# air_quality_monitor_add_esp32_chip.net
KiCad netlist of a schematic drawn in Altium Designer
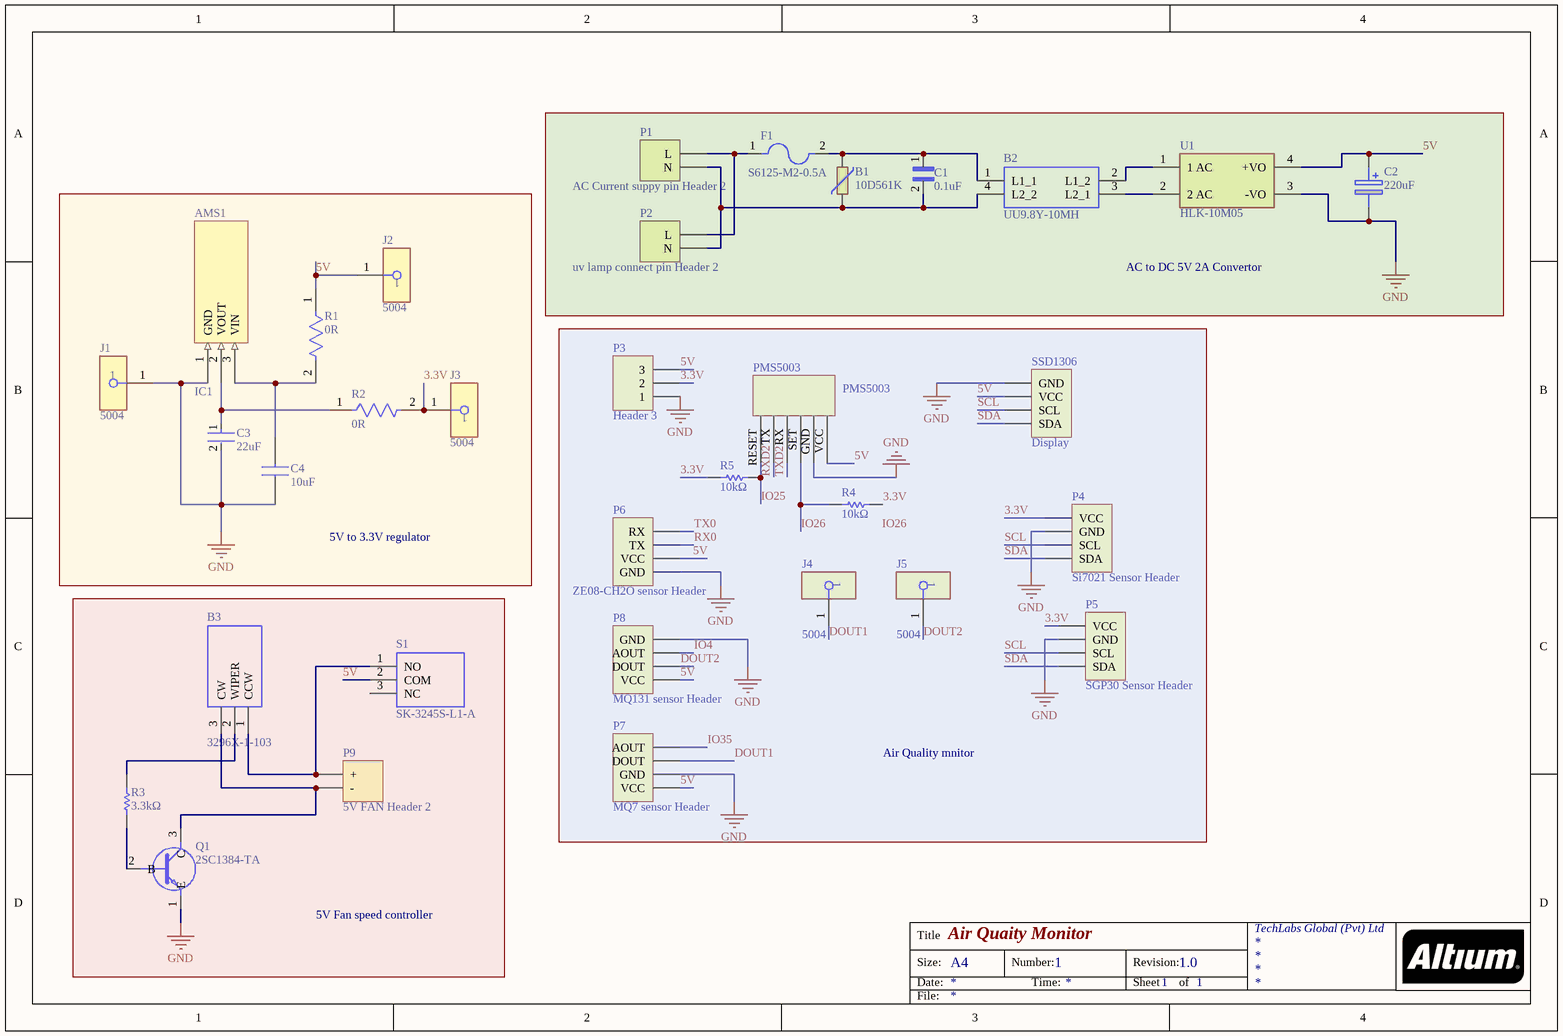
[diagram p0: air quality monitor add esp32 chip.SchDoc]

(export (version "E")
  (design (tool "Eeschema 10.0.6"))
  (components
    (comp (ref "AMS1")
      (value "IC1")
      (footprint "SOT89-150P350X150-3N")
      (fields
        (field (name "MANUFACTURER") "YONGYUTAI")
        (field (name "MFR. PART #") "AMS1117-3.3")
        (field (name "LCSC PART #") "C2904742")
      )
      (libsource (lib "AMS1117-3.3") (part "IC?"))
    )
    (comp (ref "B1")
      (value "10D561K")
      (footprint "10D561K")
      (description "920V 42.3J 180pF@1kHz 460V 350V 504V~616V 2.5kA Plugin Varistors ROHS")
      (fields (field (name "LCSC PART #") "C113236") (field (name "MANUFACTURER") "Hongzhi Elec"))
      (libsource (lib "10D561K") (part "10D561K"))
    )
    (comp (ref "B2")
      (value "UU9.8Y-10MH")
      (footprint "UU98Y10MH")
      (description "10mH@1kHz 1.2Ω 2 500mA 50V Plugin Common Mode Filters ROHS")
      (fields
        (field (name "MANUFACTURER") "FH (Guangdong Fenghua Advanced Tech)")
        (field (name "LCSC PART#") "C75192")
      )
      (libsource (lib "UU9.8Y-10MH") (part "UU9.8Y-10MH"))
    )
    (comp (ref "B3")
      (value "3296X-1-103")
      (footprint "3296X1223LF")
      (description "±10% 10kΩ Plugin Variable Resistors/Potentiometers ROHS")
      (fields
        (field (name "MANUFACTURER") "BOCHEN(Chengdu Guosheng Tech)")
        (field (name "LCSC PART #") "C118955")
      )
      (libsource (lib "3296X-1-103") (part "3296X-1-103"))
    )
    (comp (ref "C1")
      (value "0.1uF")
      (footprint "MPX-104K275VAC-C-D2")
      (description "0.1uF ±10% -40℃~+110℃ X2 275VAC Radial Leaded,P=15mm Suppression Capacitors ROHS")
      (fields (field (name "LCSC PART #") "C3249976") (field (name "MANUFACTURER") "CORETONG"))
      (libsource (lib "MPX-104K275VAC-C-D2") (part "MPX-104K275VAC-C-D2"))
    )
    (comp (ref "C2")
      (value "220uF")
      (footprint "CAPAE830X1050N")
      (fields
        (field (name "MANUFACTURER") "Nichicon")
        (field (name "MFR.PART #") "UUR1C221MNL1GS")
        (field (name "LCSC PART#") "C445237")
      )
      (libsource (lib "UUR1C221MNL1GS") (part "UUR1C221MNL1GS"))
    )
    (comp (ref "C3")
      (value "22uF")
      (footprint "FP-GRM219-0_2-0_15-IPC_A")
      (description "Chip Multilayer Ceramic Capacitors for General Purpose, 0805, 22uF, X5R, 15%, 20%, 16V")
      (fields (field (name "MFR. PART #") "GRM219R61C226ME15L") (field (name "LCSC PART #") "C162295"))
      (libsource (lib "Altium Content Vault") (part "b4654b650e69147ec39a6b967a45e02"))
    )
    (comp (ref "C4")
      (value "10uF")
      (footprint "CAPC1005X70N")
      (description "6.3V 10uF X5R ±20% 0402 Multilayer Ceramic Capacitors MLCC - SMD/SMT ROHS")
      (fields
        (field (name "MANUFACTURER") "Samsung Electro-Mechanics")
        (field (name "MFR. PART #") "CL05A106MQ5NUNC")
      )
      (libsource (lib "CL05A106MQ5NUNC") (part "CL05A106MQ5NUNC"))
    )
    (comp (ref "F1")
      (value "S6125-M2-0.5A")
      (footprint "CAPC6125X25N")
      (description "SMD Fuses ROHS")
      (fields (field (name "LCSC PART #") "C845172") (field (name "MANUFACTURER") "SART(Nanjing Sart Tech)"))
      (libsource (lib "S6125-M2-0.5A") (part "S6125-M2-0.5A"))
    )
    (comp (ref "J1")
      (value "5004")
      (footprint "FP-5004-MFG")
      (description "PC TEST POINT MINIATURE YELLOW")
      (fields (field (name "MANUFACTURER") "Keystone") (field (name "LCSC PART #") "C2906762"))
      (libsource (lib "") (part "98815daf2f2c152b0c43f5ab9800df6_2"))
    )
    (comp (ref "J2")
      (value "5004")
      (footprint "FP-5004-MFG")
      (description "PC TEST POINT MINIATURE YELLOW")
      (fields (field (name "MANUFACTURER") "Keystone") (field (name "LCSC PART #") "C2906762"))
      (libsource (lib "Altium Content Vault") (part "98815daf2f2c152b0c43f5ab9800df6"))
    )
    (comp (ref "J3")
      (value "5004")
      (footprint "FP-5004-MFG")
      (description "PC TEST POINT MINIATURE YELLOW")
      (fields (field (name "MANUFACTURER") "Keystone") (field (name "LCSC PART #") "C2906762"))
      (libsource (lib "Altium Content Vault") (part "98815daf2f2c152b0c43f5ab9800df6"))
    )
    (comp (ref "J4")
      (value "5004")
      (footprint "FP-5004-MFG")
      (description "PC TEST POINT MINIATURE YELLOW")
      (fields (field (name "MANUFACTURER") "Keystone") (field (name "LCSC PART #") "C2906762"))
      (libsource (lib "") (part "98815daf2f2c152b0c43f5ab9800df6_1"))
    )
    (comp (ref "J5")
      (value "5004")
      (footprint "FP-5004-MFG")
      (description "PC TEST POINT MINIATURE YELLOW")
      (fields (field (name "MANUFACTURER") "Keystone") (field (name "LCSC PART #") "C2906762"))
      (libsource (lib "") (part "98815daf2f2c152b0c43f5ab9800df6_1"))
    )
    (comp (ref "P1")
      (value "AC Current suppy pin Header 2")
      (footprint "HDR1X2")
      (description "Header, 2-Pin")
      (fields (field (name "PUBLISHER") "Altium Limited"))
      (libsource (lib "Miscellaneous Connectors") (part "Header 2"))
    )
    (comp (ref "P2")
      (value "uv lamp connect pin Header 2")
      (footprint "HDR1X2")
      (description "Header, 2-Pin")
      (fields (field (name "PUBLISHER") "Altium Limited"))
      (libsource (lib "Miscellaneous Connectors") (part "Header 2"))
    )
    (comp (ref "P3")
      (value "Header 3")
      (footprint "HDR1X3")
      (description "Header, 3-Pin")
      (fields (field (name "PUBLISHER") "Altium Limited"))
      (libsource (lib "Miscellaneous Connectors") (part "Header 3"))
    )
    (comp (ref "P4")
      (value "Si7021 Sensor Header")
      (footprint "HDR1X4")
      (description "Header, 4-Pin")
      (libsource (lib "") (part "Header 4_1"))
    )
    (comp (ref "P5")
      (value "SGP30 Sensor Header")
      (footprint "HDR1X4")
      (description "Header, 4-Pin")
      (fields (field (name "PUBLISHER") "Altium Limited"))
      (libsource (lib "") (part "Header 4_1"))
    )
    (comp (ref "P6")
      (value "ZE08-CH2O sensor Header")
      (footprint "HDR1X4")
      (description "- Sensor Modules ROHS")
      (fields
        (field (name "MFR.PART #") "ZE08-CH2O")
        (field (name "MANUFACTURER") "Zhengzhou Winsen Elec Tech")
      )
      (libsource (lib "") (part "Header 4_4"))
    )
    (comp (ref "P7")
      (value "MQ7 sensor Header")
      (footprint "HDR1X4")
      (description "Header, 4-Pin")
      (fields (field (name "PUBLISHER") "Altium Limited"))
      (libsource (lib "Miscellaneous Connectors") (part "Header 4"))
    )
    (comp (ref "P8")
      (value "MQ131 sensor Header")
      (footprint "HDR1X4")
      (description "Header, 4-Pin")
      (fields (field (name "PUBLISHER") "Altium Limited"))
      (libsource (lib "") (part "Header 4_2"))
    )
    (comp (ref "P9")
      (value "5V FAN Header 2")
      (footprint "HDR1X2")
      (description "Header, 2-Pin")
      (fields (field (name "PUBLISHER") "Altium Limited"))
      (libsource (lib "") (part "Header 2_1"))
    )
    (comp (ref "PMS5003")
      (value "PMS5003")
      (footprint "PMS5003 PM2.5 Sensor")
      (description "PMS5003 Sensor Modules ROHS")
      (fields (field (name "MANUFACTURER") "Beijing Plantower") (field (name "LCSC PART#") "C91431"))
      (libsource (lib "DIY Air Quality Monitor Library") (part "PMS5003 PM2.5 Sensor"))
    )
    (comp (ref "Q1")
      (value "2SC1384-TA")
      (footprint "2SC1384-TA")
      (description "TO-92-3 Bipolar Transistors - BJT ROHS")
      (fields
        (field (name "MANUFACTURER") "Jiangsu Changjing Electronics Technology Co., Ltd.")
        (field (name "LCSC PART #") "C2910422")
      )
      (libsource (lib "2SC1384-TA") (part "2SC1384-TA"))
    )
    (comp (ref "R1")
      (value "0R")
      (footprint "FP-RC0402-0_4-IPC_A")
      (description "RES SMD 0 OHM JUMPER 1/16W 0402")
      (fields (field (name "MANUFACTURER") "Yageo") (field (name "LCSC PART #") "C106231"))
      (libsource (lib "Altium Content Vault") (part "1029c3af85768c4190bb7ad29bc67b5"))
    )
    (comp (ref "R2")
      (value "0R")
      (footprint "FP-RC0402-0_4-IPC_A")
      (description "RES SMD 0 OHM JUMPER 1/16W 0402")
      (fields (field (name "MANUFACTURER") "Yageo") (field (name "LCSC PART #") "C106231"))
      (libsource (lib "Altium Content Vault") (part "1029c3af85768c4190bb7ad29bc67b5"))
    )
    (comp (ref "R3")
      (value "3.3kΩ")
      (footprint "RESC1608X55X25ML10T15")
      (fields
        (field (name "MANUFACTURER") "YAGEO")
        (field (name "MFR. PART #") "RC0603FR-073K3L")
        (field (name "LCSC PART #") "C108078")
      )
      (libsource (lib "Altium Content Vault") (part "RES-2"))
    )
    (comp (ref "R4")
      (value "10kΩ")
      (footprint "RESC1005X40X25LL05T10")
      (description "62.5mW 50V ±100ppm/℃ ±1% -55℃~+155℃ 10kΩ 0402 Chip Resistor - Surface Mount ROHS")
      (fields (field (name "MFR. PART #") "RC0402FR-0710KL") (field (name "MANUFACTURER") "Yageo / Phycomp"))
      (libsource (lib "Altium Content Vault") (part "RES"))
    )
    (comp (ref "R5")
      (value "10kΩ")
      (footprint "RESC1005X40X25LL05T10")
      (description "62.5mW 50V ±100ppm/℃ ±1% -55℃~+155℃ 10kΩ 0402 Chip Resistor - Surface Mount ROHS")
      (fields (field (name "MFR. PART #") "RC0402FR-0710KL") (field (name "MANUFACTURER") "Yageo / Phycomp"))
      (libsource (lib "Altium Content Vault") (part "RES"))
    )
    (comp (ref "S1")
      (value "SK-3245S-L1-A")
      (footprint "SK3245SL1A")
      (fields (field (name "MANUFACTURER") "XKB Connectivity") (field (name "LCSC PART#") "C405951"))
      (libsource (lib "SK-3245S-L1-A") (part "SK-3245S-L1-A"))
    )
    (comp (ref "SSD1306")
      (value "Display")
      (footprint "HDR1X4")
      (description "Header, 4-Pin")
      (fields (field (name "PUBLISHER") "Altium Limited"))
      (libsource (lib "") (part "Header 4_3"))
    )
    (comp (ref "U1")
      (value "HLK-10M05")
      (footprint "FP-HLK-10M05-MFG")
      (description "5V 2A 90VAC~265VAC 1 120V~350V Isolated Regulated 10W AC-DC 80% Plugin Power Modules ROHS")
      (fields (field (name "MANUFACTURER") "HI-LINK") (field (name "LCSC PART#") "C403745"))
      (libsource (lib "Altium Content Vault") (part "a65b17ccb3a75dffb3c3e849074403b"))
    )
  )
  (nets
    (net (code "1") (name "/3.3V") (class "Default")
      (node (ref "J3") (pin "1") (pinfunction "1_1") (pintype "passive"))
      (node (ref "P3") (pin "2") (pinfunction "2_2") (pintype "passive"))
      (node (ref "P4") (pin "1") (pinfunction "VCC_1") (pintype "passive"))
      (node (ref "P5") (pin "1") (pinfunction "VCC_1") (pintype "passive"))
      (node (ref "R2") (pin "2") (pinfunction "2_2") (pintype "passive"))
      (node (ref "R4") (pin "2") (pinfunction "2_2") (pintype "passive"))
      (node (ref "R5") (pin "1") (pinfunction "1_1") (pintype "passive"))
    )
    (net (code "2") (name "/5V") (class "Default")
      (node (ref "C2") (pin "1") (pinfunction "+_1") (pintype "passive"))
      (node (ref "J2") (pin "1") (pinfunction "1_1") (pintype "passive"))
      (node (ref "P3") (pin "3") (pinfunction "3_3") (pintype "passive"))
      (node (ref "P6") (pin "2") (pinfunction "VCC_2") (pintype "passive"))
      (node (ref "P7") (pin "1") (pinfunction "VCC_1") (pintype "passive"))
      (node (ref "P8") (pin "1") (pinfunction "VCC_1") (pintype "passive"))
      (node (ref "PMS5003") (pin "VCC") (pintype "passive"))
      (node (ref "R1") (pin "1") (pinfunction "1_1") (pintype "passive"))
      (node (ref "S1") (pin "2") (pinfunction "COM_2") (pintype "passive"))
      (node (ref "SSD1306") (pin "2") (pinfunction "VCC_2") (pintype "passive"))
      (node (ref "U1") (pin "4") (pinfunction "+VO_4") (pintype "power_in"))
    )
    (net (code "3") (name "/DOUT1") (class "Default")
      (node (ref "J4") (pin "1") (pinfunction "1_1") (pintype "passive"))
      (node (ref "P7") (pin "3") (pinfunction "DOUT_3") (pintype "passive"))
    )
    (net (code "4") (name "/DOUT2") (class "Default")
      (node (ref "J5") (pin "1") (pinfunction "1_1") (pintype "passive"))
      (node (ref "P8") (pin "2") (pinfunction "DOUT_2") (pintype "passive"))
    )
    (net (code "5") (name "/IO4") (class "Default")
      (node (ref "P8") (pin "3") (pinfunction "AOUT_3") (pintype "passive"))
    )
    (net (code "6") (name "/IO25") (class "Default")
      (node (ref "PMS5003") (pin "RESET") (pintype "passive"))
      (node (ref "R5") (pin "2") (pinfunction "2_2") (pintype "passive"))
    )
    (net (code "7") (name "/IO26") (class "Default")
      (node (ref "PMS5003") (pin "SET") (pintype "passive"))
      (node (ref "R4") (pin "1") (pinfunction "1_1") (pintype "passive"))
    )
    (net (code "8") (name "/IO35") (class "Default")
      (node (ref "P7") (pin "4") (pinfunction "AOUT_4") (pintype "passive"))
    )
    (net (code "9") (name "/RX0") (class "Default")
      (node (ref "P6") (pin "3") (pinfunction "TX_3") (pintype "passive"))
    )
    (net (code "10") (name "/RXD2") (class "Default") (node (ref "PMS5003") (pin "TX") (pintype "passive")))
    (net (code "11") (name "/SCL") (class "Default")
      (node (ref "P4") (pin "3") (pinfunction "SCL_3") (pintype "passive"))
      (node (ref "P5") (pin "3") (pinfunction "SCL_3") (pintype "passive"))
      (node (ref "SSD1306") (pin "3") (pinfunction "SCL_3") (pintype "passive"))
    )
    (net (code "12") (name "/SDA") (class "Default")
      (node (ref "P4") (pin "4") (pinfunction "SDA_4") (pintype "passive"))
      (node (ref "P5") (pin "4") (pinfunction "SDA_4") (pintype "passive"))
      (node (ref "SSD1306") (pin "4") (pinfunction "SDA_4") (pintype "passive"))
    )
    (net (code "13") (name "/TX0") (class "Default")
      (node (ref "P6") (pin "4") (pinfunction "RX_4") (pintype "passive"))
    )
    (net (code "14") (name "/TXD2") (class "Default") (node (ref "PMS5003") (pin "RX") (pintype "passive")))
    (net (code "15") (name "GND") (class "Default")
      (node (ref "AMS1") (pin "1") (pinfunction "GND_1") (pintype "input"))
      (node (ref "C2") (pin "2") (pinfunction "-_2") (pintype "passive"))
      (node (ref "C3") (pin "2") (pinfunction "2_2") (pintype "passive"))
      (node (ref "C4") (pin "1") (pinfunction "1_1") (pintype "passive"))
      (node (ref "J1") (pin "1") (pinfunction "1_1") (pintype "passive"))
      (node (ref "P3") (pin "1") (pinfunction "1_1") (pintype "passive"))
      (node (ref "P4") (pin "2") (pinfunction "GND_2") (pintype "passive"))
      (node (ref "P5") (pin "2") (pinfunction "GND_2") (pintype "passive"))
      (node (ref "P6") (pin "1") (pinfunction "GND_1") (pintype "passive"))
      (node (ref "P7") (pin "2") (pinfunction "GND_2") (pintype "passive"))
      (node (ref "P8") (pin "4") (pinfunction "GND_4") (pintype "passive"))
      (node (ref "PMS5003") (pin "GND") (pintype "passive"))
      (node (ref "Q1") (pin "1") (pinfunction "E_1") (pintype "passive"))
      (node (ref "SSD1306") (pin "1") (pinfunction "GND_1") (pintype "passive"))
      (node (ref "U1") (pin "3") (pinfunction "-VO_3") (pintype "power_in"))
    )
    (net (code "16") (name "Net-(AMS1-VIN)") (class "Default")
      (node (ref "AMS1") (pin "3") (pinfunction "VIN_3") (pintype "input"))
      (node (ref "C4") (pin "2") (pinfunction "2_2") (pintype "passive"))
      (node (ref "R1") (pin "2") (pinfunction "2_2") (pintype "passive"))
    )
    (net (code "17") (name "Net-(AMS1-VOUT)") (class "Default")
      (node (ref "AMS1") (pin "2") (pinfunction "VOUT_2") (pintype "input"))
      (node (ref "C3") (pin "1") (pinfunction "1_1") (pintype "passive"))
      (node (ref "R2") (pin "1") (pinfunction "1_1") (pintype "passive"))
    )
    (net (code "18") (name "Net-(B2-L1_1)") (class "Default")
      (node (ref "B1") (pin "1") (pinfunction "1_1") (pintype "passive"))
      (node (ref "B2") (pin "1") (pinfunction "L1_1_1") (pintype "passive"))
      (node (ref "C1") (pin "1") (pinfunction "1_1") (pintype "passive"))
      (node (ref "F1") (pin "2") (pinfunction "2_2") (pintype "passive"))
    )
    (net (code "19") (name "Net-(B2-L1_2)") (class "Default")
      (node (ref "B2") (pin "2") (pinfunction "L1_2_2") (pintype "passive"))
      (node (ref "U1") (pin "1") (pinfunction "1_AC_1") (pintype "passive"))
    )
    (net (code "20") (name "Net-(B2-L2_1)") (class "Default")
      (node (ref "B2") (pin "3") (pinfunction "L2_1_3") (pintype "passive"))
      (node (ref "U1") (pin "2") (pinfunction "2_AC_2") (pintype "passive"))
    )
    (net (code "21") (name "Net-(B2-L2_2)") (class "Default")
      (node (ref "B1") (pin "2") (pinfunction "2_2") (pintype "passive"))
      (node (ref "B2") (pin "4") (pinfunction "L2_2_4") (pintype "passive"))
      (node (ref "C1") (pin "2") (pinfunction "2_2") (pintype "passive"))
      (node (ref "P1") (pin "1") (pinfunction "N_1") (pintype "passive"))
      (node (ref "P2") (pin "1") (pinfunction "N_1") (pintype "passive"))
    )
    (net (code "22") (name "Net-(B3-CCW)") (class "Default")
      (node (ref "B3") (pin "1") (pinfunction "CCW_1") (pintype "passive"))
      (node (ref "P9") (pin "1") (pinfunction "+_1") (pintype "passive"))
      (node (ref "S1") (pin "1") (pinfunction "NO_1") (pintype "passive"))
    )
    (net (code "23") (name "Net-(B3-CW)") (class "Default")
      (node (ref "B3") (pin "3") (pinfunction "CW_3") (pintype "passive"))
      (node (ref "P9") (pin "2") (pinfunction "-_2") (pintype "passive"))
      (node (ref "Q1") (pin "3") (pinfunction "C_3") (pintype "passive"))
    )
    (net (code "24") (name "Net-(B3-WIPER)") (class "Default")
      (node (ref "B3") (pin "2") (pinfunction "WIPER_2") (pintype "passive"))
      (node (ref "R3") (pin "2") (pinfunction "2_2") (pintype "passive"))
    )
    (net (code "25") (name "Net-(P1-L)") (class "Default")
      (node (ref "F1") (pin "1") (pinfunction "1_1") (pintype "passive"))
      (node (ref "P1") (pin "2") (pinfunction "L_2") (pintype "passive"))
      (node (ref "P2") (pin "2") (pinfunction "L_2") (pintype "passive"))
    )
    (net (code "26") (name "Net-(Q1-B)") (class "Default")
      (node (ref "Q1") (pin "2") (pinfunction "B_2") (pintype "passive"))
      (node (ref "R3") (pin "1") (pinfunction "1_1") (pintype "passive"))
    )
    (net (code "27") (name "unconnected-(S1-NC-Pad3)") (class "Default")
      (node (ref "S1") (pin "3") (pinfunction "NC_3") (pintype "passive"))
    )
  )
)
